# Pro_Mini_Sensor_Breakout.net
KiCad netlist of a schematic drawn in EAGLE
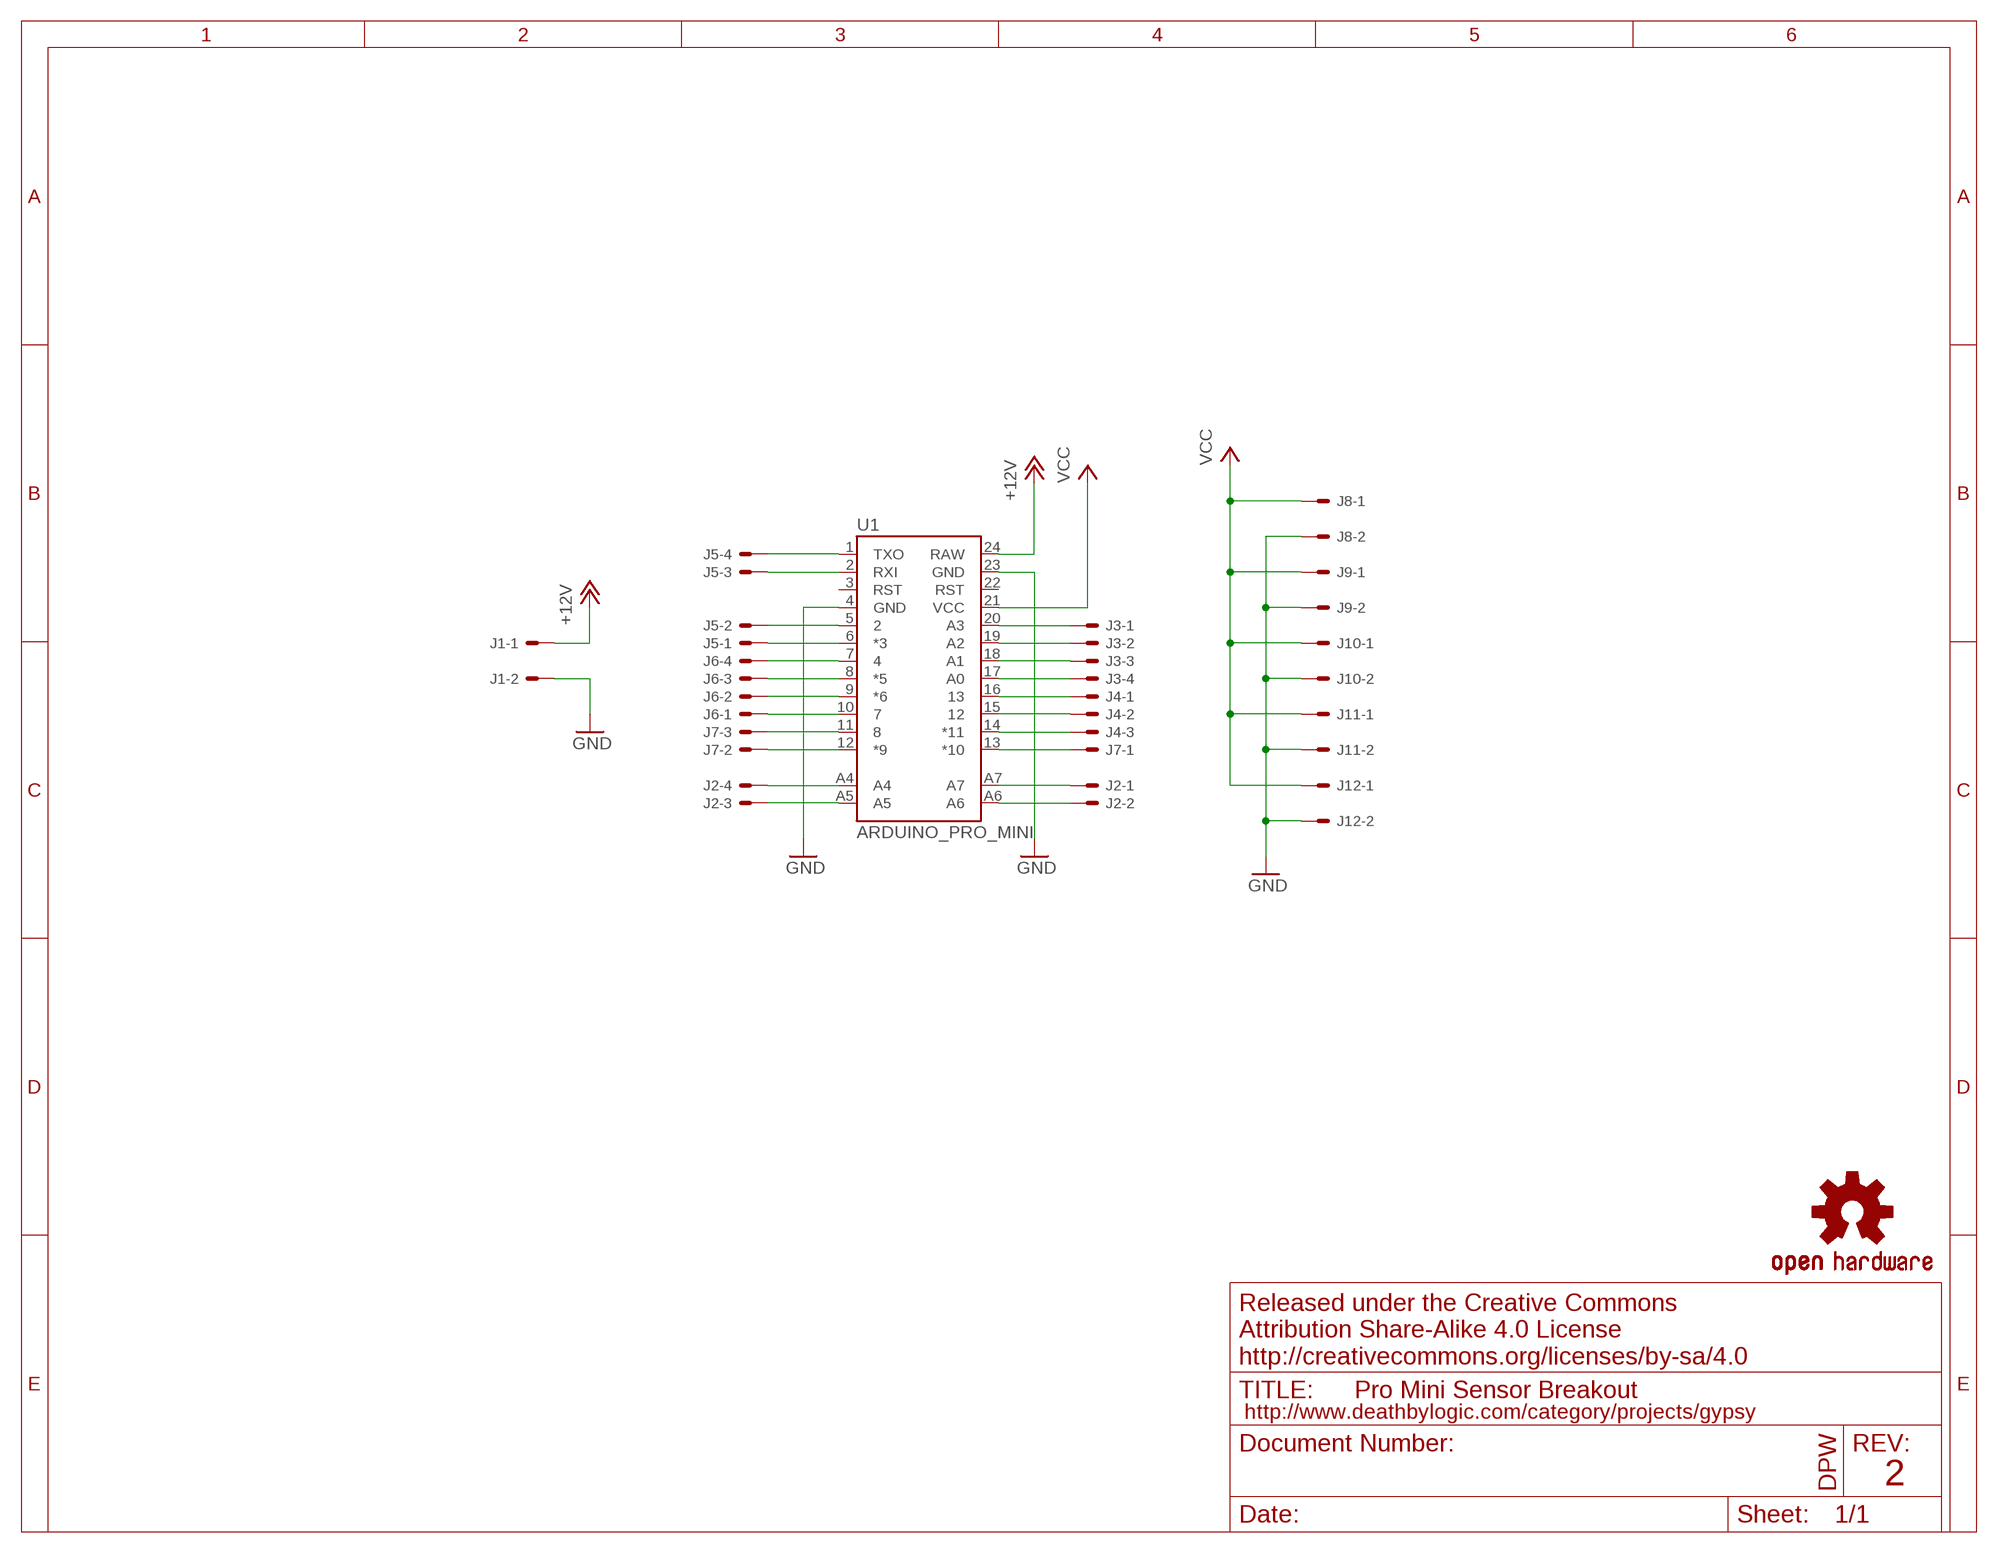
[diagram p0: schematic, sheet 1]

(export (version "E")
  (design (tool "Eeschema 10.0.6"))
  (components
    (comp (ref "J1")
      (value "22-27-2021-02")
      (footprint "eagle-import:6410-02")
      (libsource (lib "eagle-import") (part "22-?-0227-2021"))
    )
    (comp (ref "J2")
      (value "22-27-2041-04")
      (footprint "eagle-import:6410-04")
      (libsource (lib "eagle-import") (part "22-?-0427-2041"))
    )
    (comp (ref "J3")
      (value "22-27-2041-04")
      (footprint "eagle-import:6410-04")
      (libsource (lib "eagle-import") (part "22-?-0427-2041"))
    )
    (comp (ref "J4")
      (value "22-27-2031-03")
      (footprint "eagle-import:6410-03")
      (libsource (lib "eagle-import") (part "22-?-0327-2031"))
    )
    (comp (ref "J5")
      (value "22-27-2041-04")
      (footprint "eagle-import:6410-04")
      (libsource (lib "eagle-import") (part "22-?-0427-2041"))
    )
    (comp (ref "J6")
      (value "22-27-2041-04")
      (footprint "eagle-import:6410-04")
      (libsource (lib "eagle-import") (part "22-?-0427-2041"))
    )
    (comp (ref "J7")
      (value "22-27-2031-03")
      (footprint "eagle-import:6410-03")
      (libsource (lib "eagle-import") (part "22-?-0327-2031"))
    )
    (comp (ref "J8")
      (value "22-27-2021-02")
      (footprint "eagle-import:6410-02")
      (libsource (lib "eagle-import") (part "22-?-0227-2021"))
    )
    (comp (ref "J9")
      (value "22-27-2021-02")
      (footprint "eagle-import:6410-02")
      (libsource (lib "eagle-import") (part "22-?-0227-2021"))
    )
    (comp (ref "J10")
      (value "22-27-2021-02")
      (footprint "eagle-import:6410-02")
      (libsource (lib "eagle-import") (part "22-?-0227-2021"))
    )
    (comp (ref "J11")
      (value "22-27-2021-02")
      (footprint "eagle-import:6410-02")
      (libsource (lib "eagle-import") (part "22-?-0227-2021"))
    )
    (comp (ref "J12")
      (value "22-27-2021-02")
      (footprint "eagle-import:6410-02")
      (libsource (lib "eagle-import") (part "22-?-0227-2021"))
    )
    (comp (ref "LOGO2")
      (value "OSHW-LOGOM")
      (footprint "eagle-import:OSHW-LOGO-M")
      (libsource (lib "eagle-import") (part "OSHW-LOGOM"))
    )
    (comp (ref "U$6")
      (value "PENGUIN_LOGOSILKSCREEN")
      (footprint "eagle-import:PENGUIN_SILKSCREEN")
      (libsource (lib "eagle-import") (part "PENGUIN_LOGOSILKSCREEN"))
    )
    (comp (ref "U1")
      (value "ARDUINO_PRO_MINI")
      (footprint "eagle-import:ARDUINO_PRO_MINI")
      (libsource (lib "eagle-import") (part "ARDUINO_PRO_MINI"))
    )
  )
  (nets
    (net (code "1") (name "+12V") (class "Default")
      (node (ref "J1") (pin "1") (pinfunction "S_1") (pintype "passive"))
      (node (ref "U1") (pin "24") (pinfunction "RAW_24") (pintype "bidirectional"))
    )
    (net (code "2") (name "GND") (class "Default")
      (node (ref "J1") (pin "2") (pinfunction "S_2") (pintype "passive"))
      (node (ref "J10") (pin "2") (pinfunction "S_2") (pintype "passive"))
      (node (ref "J11") (pin "2") (pinfunction "S_2") (pintype "passive"))
      (node (ref "J12") (pin "2") (pinfunction "S_2") (pintype "passive"))
      (node (ref "J8") (pin "2") (pinfunction "S_2") (pintype "passive"))
      (node (ref "J9") (pin "2") (pinfunction "S_2") (pintype "passive"))
      (node (ref "U1") (pin "23") (pinfunction "GND_23") (pintype "bidirectional"))
      (node (ref "U1") (pin "4") (pinfunction "GND_4") (pintype "bidirectional"))
    )
    (net (code "3") (name "Net-(J2A-S)") (class "Default")
      (node (ref "J2") (pin "1") (pinfunction "S_1") (pintype "passive"))
      (node (ref "U1") (pin "A7") (pinfunction "A7_A7") (pintype "bidirectional"))
    )
    (net (code "4") (name "Net-(J2B-S)") (class "Default")
      (node (ref "J2") (pin "2") (pinfunction "S_2") (pintype "passive"))
      (node (ref "U1") (pin "A6") (pinfunction "A6_A6") (pintype "bidirectional"))
    )
    (net (code "5") (name "Net-(J2C-S)") (class "Default")
      (node (ref "J2") (pin "3") (pinfunction "S_3") (pintype "passive"))
      (node (ref "U1") (pin "A5") (pinfunction "A5_A5") (pintype "bidirectional"))
    )
    (net (code "6") (name "Net-(J2D-S)") (class "Default")
      (node (ref "J2") (pin "4") (pinfunction "S_4") (pintype "passive"))
      (node (ref "U1") (pin "A4") (pinfunction "A4_A4") (pintype "bidirectional"))
    )
    (net (code "7") (name "Net-(J3A-S)") (class "Default")
      (node (ref "J3") (pin "1") (pinfunction "S_1") (pintype "passive"))
      (node (ref "U1") (pin "20") (pinfunction "A3_20") (pintype "bidirectional"))
    )
    (net (code "8") (name "Net-(J3B-S)") (class "Default")
      (node (ref "J3") (pin "2") (pinfunction "S_2") (pintype "passive"))
      (node (ref "U1") (pin "19") (pinfunction "A2_19") (pintype "bidirectional"))
    )
    (net (code "9") (name "Net-(J3C-S)") (class "Default")
      (node (ref "J3") (pin "3") (pinfunction "S_3") (pintype "passive"))
      (node (ref "U1") (pin "18") (pinfunction "A1_18") (pintype "bidirectional"))
    )
    (net (code "10") (name "Net-(J3D-S)") (class "Default")
      (node (ref "J3") (pin "4") (pinfunction "S_4") (pintype "passive"))
      (node (ref "U1") (pin "17") (pinfunction "A0_17") (pintype "bidirectional"))
    )
    (net (code "11") (name "Net-(J4A-S)") (class "Default")
      (node (ref "J4") (pin "1") (pinfunction "S_1") (pintype "passive"))
      (node (ref "U1") (pin "16") (pinfunction "13_16") (pintype "bidirectional"))
    )
    (net (code "12") (name "Net-(J4B-S)") (class "Default")
      (node (ref "J4") (pin "2") (pinfunction "S_2") (pintype "passive"))
      (node (ref "U1") (pin "15") (pinfunction "12_15") (pintype "bidirectional"))
    )
    (net (code "13") (name "Net-(J4C-S)") (class "Default")
      (node (ref "J4") (pin "3") (pinfunction "S_3") (pintype "passive"))
      (node (ref "U1") (pin "14") (pinfunction "*11_14") (pintype "bidirectional"))
    )
    (net (code "14") (name "Net-(J5A-S)") (class "Default")
      (node (ref "J5") (pin "1") (pinfunction "S_1") (pintype "passive"))
      (node (ref "U1") (pin "6") (pinfunction "*3_6") (pintype "bidirectional"))
    )
    (net (code "15") (name "Net-(J5B-S)") (class "Default")
      (node (ref "J5") (pin "2") (pinfunction "S_2") (pintype "passive"))
      (node (ref "U1") (pin "5") (pinfunction "2_5") (pintype "bidirectional"))
    )
    (net (code "16") (name "Net-(J5C-S)") (class "Default")
      (node (ref "J5") (pin "3") (pinfunction "S_3") (pintype "passive"))
      (node (ref "U1") (pin "2") (pinfunction "RXI_2") (pintype "bidirectional"))
    )
    (net (code "17") (name "Net-(J5D-S)") (class "Default")
      (node (ref "J5") (pin "4") (pinfunction "S_4") (pintype "passive"))
      (node (ref "U1") (pin "1") (pinfunction "TXO_1") (pintype "bidirectional"))
    )
    (net (code "18") (name "Net-(J6A-S)") (class "Default")
      (node (ref "J6") (pin "1") (pinfunction "S_1") (pintype "passive"))
      (node (ref "U1") (pin "10") (pinfunction "7_10") (pintype "bidirectional"))
    )
    (net (code "19") (name "Net-(J6B-S)") (class "Default")
      (node (ref "J6") (pin "2") (pinfunction "S_2") (pintype "passive"))
      (node (ref "U1") (pin "9") (pinfunction "*6_9") (pintype "bidirectional"))
    )
    (net (code "20") (name "Net-(J6C-S)") (class "Default")
      (node (ref "J6") (pin "3") (pinfunction "S_3") (pintype "passive"))
      (node (ref "U1") (pin "8") (pinfunction "*5_8") (pintype "bidirectional"))
    )
    (net (code "21") (name "Net-(J6D-S)") (class "Default")
      (node (ref "J6") (pin "4") (pinfunction "S_4") (pintype "passive"))
      (node (ref "U1") (pin "7") (pinfunction "4_7") (pintype "bidirectional"))
    )
    (net (code "22") (name "Net-(J7A-S)") (class "Default")
      (node (ref "J7") (pin "1") (pinfunction "S_1") (pintype "passive"))
      (node (ref "U1") (pin "13") (pinfunction "*10_13") (pintype "bidirectional"))
    )
    (net (code "23") (name "Net-(J7B-S)") (class "Default")
      (node (ref "J7") (pin "2") (pinfunction "S_2") (pintype "passive"))
      (node (ref "U1") (pin "12") (pinfunction "*9_12") (pintype "bidirectional"))
    )
    (net (code "24") (name "Net-(J7C-S)") (class "Default")
      (node (ref "J7") (pin "3") (pinfunction "S_3") (pintype "passive"))
      (node (ref "U1") (pin "11") (pinfunction "8_11") (pintype "bidirectional"))
    )
    (net (code "25") (name "VCC") (class "Default")
      (node (ref "J10") (pin "1") (pinfunction "S_1") (pintype "passive"))
      (node (ref "J11") (pin "1") (pinfunction "S_1") (pintype "passive"))
      (node (ref "J12") (pin "1") (pinfunction "S_1") (pintype "passive"))
      (node (ref "J8") (pin "1") (pinfunction "S_1") (pintype "passive"))
      (node (ref "J9") (pin "1") (pinfunction "S_1") (pintype "passive"))
      (node (ref "U1") (pin "21") (pinfunction "VCC_21") (pintype "bidirectional"))
    )
    (net (code "26") (name "unconnected-(U1-RST-Pad3)") (class "Default")
      (node (ref "U1") (pin "3") (pinfunction "RST_3") (pintype "bidirectional"))
    )
    (net (code "27") (name "unconnected-(U1-RST-Pad22)") (class "Default")
      (node (ref "U1") (pin "22") (pinfunction "RST_22") (pintype "bidirectional"))
    )
  )
)
